# P6_FilterMode.net
KiCad netlist of a schematic drawn in Altium Designer
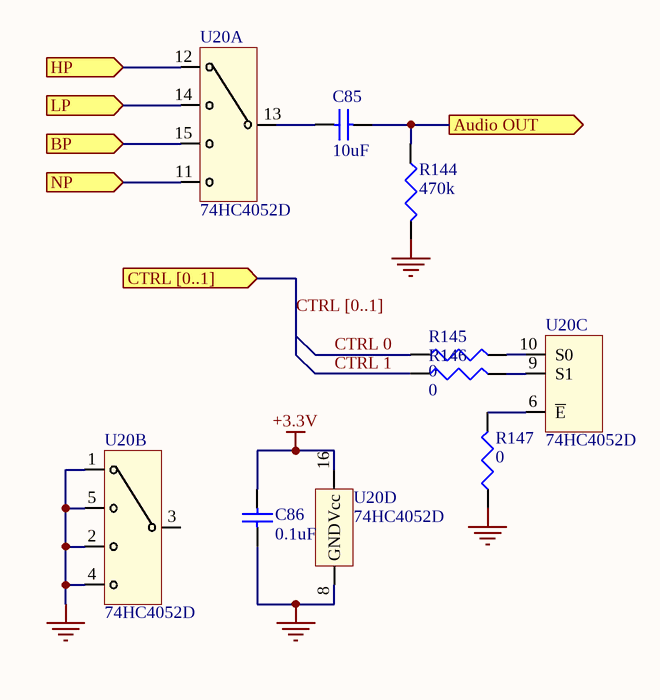
[diagram p0: P6_FilterMode.SchDoc]

(export (version "E")
  (design (tool "Eeschema 10.0.6"))
  (components
    (comp (ref "C85")
      (value "10uF")
      (footprint "CAP 0603 (1608 metric)")
      (description "Capacitor (Semiconductor SIM Model)")
      (libsource (lib "Miscellaneous Devices") (part "Cap Semi"))
    )
    (comp (ref "C86")
      (value "0.1uF")
      (footprint "CAP 0603 (1608 metric)")
      (description "Capacitor (Semiconductor SIM Model)")
      (libsource (lib "Miscellaneous Devices") (part "Cap Semi"))
    )
    (comp (ref "R144")
      (value "470k")
      (footprint "RES 0603 (1608 metric)")
      (description "Resistor")
      (libsource (lib "Miscellaneous Devices") (part "Res3"))
    )
    (comp (ref "R145")
      (value "0")
      (footprint "RES 0603 (1608 metric)")
      (description "Resistor")
      (libsource (lib "Miscellaneous Devices") (part "Res3"))
    )
    (comp (ref "R146")
      (value "0")
      (footprint "RES 0603 (1608 metric)")
      (description "Resistor")
      (libsource (lib "Miscellaneous Devices") (part "Res3"))
    )
    (comp (ref "R147")
      (value "0")
      (footprint "RES 0603 (1608 metric)")
      (description "Resistor")
      (libsource (lib "Miscellaneous Devices") (part "Res3"))
    )
    (comp (ref "U20")
      (value "74HC4052D")
      (description "Dual 4:1 Multiplexer")
      (libsource (lib "FilterPoC") (part "74HC4052D"))
    )
  )
  (nets
    (net (code "1") (name "+3.3V") (class "Default")
      (node (ref "C86") (pin "1") (pinfunction "1_1") (pintype "passive"))
      (node (ref "U20") (pin "16") (pinfunction "Vcc_16") (pintype "power_in"))
    )
    (net (code "2") (name "/Audio OUT") (class "Default")
      (node (ref "C85") (pin "1") (pinfunction "1_1") (pintype "passive"))
      (node (ref "R144") (pin "1") (pinfunction "1_1") (pintype "passive"))
    )
    (net (code "3") (name "/BP") (class "Default")
      (node (ref "U20") (pin "15") (pinfunction "1Y2_15") (pintype "passive"))
    )
    (net (code "4") (name "/CTRL 0") (class "Default")
      (node (ref "R145") (pin "1") (pinfunction "1_1") (pintype "passive"))
    )
    (net (code "5") (name "/CTRL 1") (class "Default")
      (node (ref "R146") (pin "1") (pinfunction "1_1") (pintype "passive"))
    )
    (net (code "6") (name "/HP") (class "Default")
      (node (ref "U20") (pin "12") (pinfunction "1Y0_12") (pintype "passive"))
    )
    (net (code "7") (name "/LP") (class "Default")
      (node (ref "U20") (pin "14") (pinfunction "1Y1_14") (pintype "passive"))
    )
    (net (code "8") (name "/NP") (class "Default")
      (node (ref "U20") (pin "11") (pinfunction "1Y3_11") (pintype "passive"))
    )
    (net (code "10") (name "GND") (class "Default")
      (node (ref "C86") (pin "2") (pinfunction "2_2") (pintype "passive"))
      (node (ref "R144") (pin "2") (pinfunction "2_2") (pintype "passive"))
      (node (ref "R147") (pin "1") (pinfunction "1_1") (pintype "passive"))
      (node (ref "U20") (pin "1") (pinfunction "2Y0_1") (pintype "passive"))
      (node (ref "U20") (pin "2") (pinfunction "2Y2_2") (pintype "passive"))
      (node (ref "U20") (pin "4") (pinfunction "2Y3_4") (pintype "passive"))
      (node (ref "U20") (pin "5") (pinfunction "2Y1_5") (pintype "passive"))
      (node (ref "U20") (pin "8") (pinfunction "GND_8") (pintype "power_in"))
    )
    (net (code "11") (name "Net-(U20A-1Z)") (class "Default")
      (node (ref "C85") (pin "2") (pinfunction "2_2") (pintype "passive"))
      (node (ref "U20") (pin "13") (pinfunction "1Z_13") (pintype "passive"))
    )
    (net (code "12") (name "Net-(U20C-S0)") (class "Default")
      (node (ref "R145") (pin "2") (pinfunction "2_2") (pintype "passive"))
      (node (ref "U20") (pin "10") (pinfunction "S0_10") (pintype "passive"))
    )
    (net (code "13") (name "Net-(U20C-S1)") (class "Default")
      (node (ref "R146") (pin "2") (pinfunction "2_2") (pintype "passive"))
      (node (ref "U20") (pin "9") (pinfunction "S1_9") (pintype "passive"))
    )
    (net (code "14") (name "Net-(U20C-~{E})") (class "Default")
      (node (ref "R147") (pin "2") (pinfunction "2_2") (pintype "passive"))
      (node (ref "U20") (pin "6") (pinfunction "~{E}_6") (pintype "passive"))
    )
    (net (code "15") (name "unconnected-(U20B-2Z-Pad3)") (class "Default")
      (node (ref "U20") (pin "3") (pinfunction "2Z_3") (pintype "passive"))
    )
  )
)
